# tr_auxiliary.net
KiCad netlist of a schematic drawn in Altium Designer
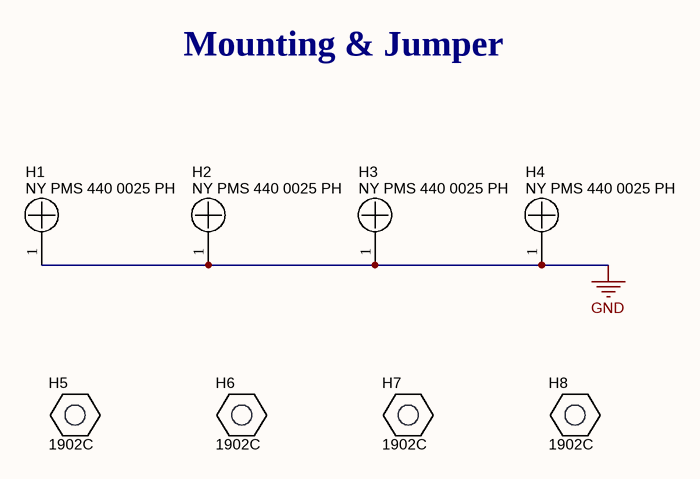
[diagram p0: tr_auxiliary.SchDoc]

(export (version "E")
  (design (tool "Eeschema 10.0.6"))
  (components
    (comp (ref "H1")
      (value "NY PMS 440 0025 PH")
      (footprint "NY PMS 440 0025 PH")
      (description "Machine Screw, Round, #4-40 x 1/4, Nylon, Philips panhead")
      (fields
        (field (name "MANUFACTURER") "B&F Fastener Supply")
        (field (name "DIGIKEYPARTNUMBER") "H542-ND")
        (field (name "SYMBOLCREATOR") "codlsc")
        (field (name "PUBLISHER") "Texas Instruments")
      )
      (libsource (lib "FAMIS") (part "NY PMS 440 0025 PH"))
    )
    (comp (ref "H2")
      (value "NY PMS 440 0025 PH")
      (footprint "NY PMS 440 0025 PH")
      (description "Machine Screw, Round, #4-40 x 1/4, Nylon, Philips panhead")
      (fields
        (field (name "MANUFACTURER") "B&F Fastener Supply")
        (field (name "DIGIKEYPARTNUMBER") "H542-ND")
        (field (name "SYMBOLCREATOR") "codlsc")
        (field (name "PUBLISHER") "Texas Instruments")
      )
      (libsource (lib "FAMIS") (part "NY PMS 440 0025 PH"))
    )
    (comp (ref "H3")
      (value "NY PMS 440 0025 PH")
      (footprint "NY PMS 440 0025 PH")
      (description "Machine Screw, Round, #4-40 x 1/4, Nylon, Philips panhead")
      (fields
        (field (name "MANUFACTURER") "B&F Fastener Supply")
        (field (name "DIGIKEYPARTNUMBER") "H542-ND")
        (field (name "SYMBOLCREATOR") "codlsc")
        (field (name "PUBLISHER") "Texas Instruments")
      )
      (libsource (lib "FAMIS") (part "NY PMS 440 0025 PH"))
    )
    (comp (ref "H4")
      (value "NY PMS 440 0025 PH")
      (footprint "NY PMS 440 0025 PH")
      (description "Machine Screw, Round, #4-40 x 1/4, Nylon, Philips panhead")
      (fields
        (field (name "MANUFACTURER") "B&F Fastener Supply")
        (field (name "DIGIKEYPARTNUMBER") "H542-ND")
        (field (name "SYMBOLCREATOR") "codlsc")
        (field (name "PUBLISHER") "Texas Instruments")
      )
      (libsource (lib "FAMIS") (part "NY PMS 440 0025 PH"))
    )
    (comp (ref "H5")
      (value "1902C")
      (footprint "Keystone_1902C")
      (description "Standoff, Hex, 0.5\"L #4-40 Nylon")
      (fields
        (field (name "MANUFACTURER") "Keystone")
        (field (name "PUBLISHER") "Texas Instruments")
        (field (name "SYMBOLCREATOR") "a0412235")
      )
      (libsource (lib "FAMIS") (part "1902C"))
    )
    (comp (ref "H6")
      (value "1902C")
      (footprint "Keystone_1902C")
      (description "Standoff, Hex, 0.5\"L #4-40 Nylon")
      (fields
        (field (name "MANUFACTURER") "Keystone")
        (field (name "PUBLISHER") "Texas Instruments")
        (field (name "SYMBOLCREATOR") "a0412235")
      )
      (libsource (lib "FAMIS") (part "1902C"))
    )
    (comp (ref "H7")
      (value "1902C")
      (footprint "Keystone_1902C")
      (description "Standoff, Hex, 0.5\"L #4-40 Nylon")
      (fields
        (field (name "MANUFACTURER") "Keystone")
        (field (name "PUBLISHER") "Texas Instruments")
        (field (name "SYMBOLCREATOR") "a0412235")
      )
      (libsource (lib "FAMIS") (part "1902C"))
    )
    (comp (ref "H8")
      (value "1902C")
      (footprint "Keystone_1902C")
      (description "Standoff, Hex, 0.5\"L #4-40 Nylon")
      (fields
        (field (name "MANUFACTURER") "Keystone")
        (field (name "PUBLISHER") "Texas Instruments")
        (field (name "SYMBOLCREATOR") "a0412235")
      )
      (libsource (lib "FAMIS") (part "1902C"))
    )
  )
  (nets
    (net (code "1") (name "GND") (class "Default")
      (node (ref "H1") (pin "1") (pinfunction "1_1") (pintype "passive"))
      (node (ref "H2") (pin "1") (pinfunction "1_1") (pintype "passive"))
      (node (ref "H3") (pin "1") (pinfunction "1_1") (pintype "passive"))
      (node (ref "H4") (pin "1") (pinfunction "1_1") (pintype "passive"))
    )
  )
)
